# RS232toUART.net
KiCad netlist of a schematic drawn in Altium Designer
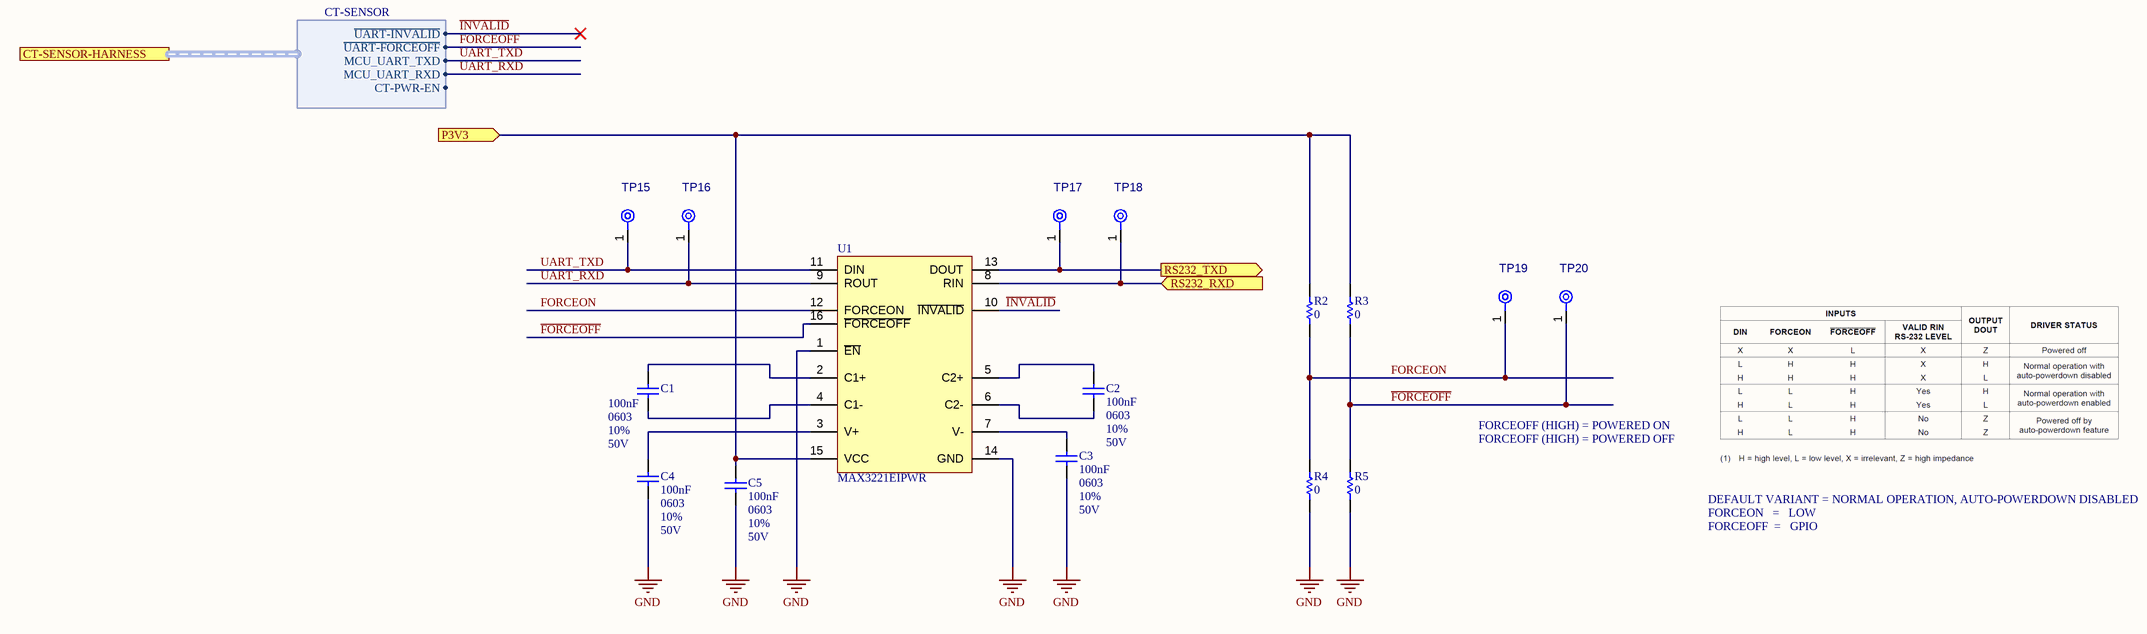
[diagram p0: RS232toUART.SchDoc]

(export (version "E")
  (design (tool "Eeschema 10.0.6"))
  (components
    (comp (ref "C1")
      (value "100nF")
      (footprint "CAPC1608X90X40ML10T20")
      (description "Chip Capacitor, 100nF, +/- 10%, 50 V, X7R 0603 (1608 Metric)")
      (fields
        (field (name "CASE/PACKAGE") "0603")
        (field (name "TOLERANCE") "10%")
        (field (name "VOLTAGE RATING") "50V")
        (field (name "Comment") "Capacitor 100nF +/- 10%, 50V, X7R, 0603")
      )
      (libsource (lib "Applied Physics Lab") (part "CAP-NP-2"))
    )
    (comp (ref "C2")
      (value "100nF")
      (footprint "CAPC1608X90X40ML10T20")
      (description "Chip Capacitor, 100nF, +/- 10%, 50 V, X7R 0603 (1608 Metric)")
      (fields
        (field (name "CASE/PACKAGE") "0603")
        (field (name "TOLERANCE") "10%")
        (field (name "VOLTAGE RATING") "50V")
        (field (name "Comment") "Capacitor 100nF +/- 10%, 50V, X7R, 0603")
      )
      (libsource (lib "Applied Physics Lab") (part "CAP-NP-2"))
    )
    (comp (ref "C3")
      (value "100nF")
      (footprint "CAPC1608X90X40ML10T20")
      (description "Chip Capacitor, 100nF, +/- 10%, 50 V, X7R 0603 (1608 Metric)")
      (fields
        (field (name "CASE/PACKAGE") "0603")
        (field (name "TOLERANCE") "10%")
        (field (name "VOLTAGE RATING") "50V")
        (field (name "Comment") "Capacitor 100nF +/- 10%, 50V, X7R, 0603")
      )
      (libsource (lib "Applied Physics Lab") (part "CAP-NP-2"))
    )
    (comp (ref "C4")
      (value "100nF")
      (footprint "CAPC1608X90X40ML10T20")
      (description "Chip Capacitor, 100nF, +/- 10%, 50 V, X7R 0603 (1608 Metric)")
      (fields
        (field (name "CASE/PACKAGE") "0603")
        (field (name "TOLERANCE") "10%")
        (field (name "VOLTAGE RATING") "50V")
        (field (name "Comment") "Capacitor 100nF +/- 10%, 50V, X7R, 0603")
      )
      (libsource (lib "Applied Physics Lab") (part "CAP-NP-2"))
    )
    (comp (ref "C5")
      (value "100nF")
      (footprint "CAPC1608X90X40ML10T20")
      (description "Chip Capacitor, 100nF, +/- 10%, 50 V, X7R 0603 (1608 Metric)")
      (fields
        (field (name "CASE/PACKAGE") "0603")
        (field (name "TOLERANCE") "10%")
        (field (name "VOLTAGE RATING") "50V")
        (field (name "Comment") "Capacitor 100nF +/- 10%, 50V, X7R, 0603")
      )
      (libsource (lib "Applied Physics Lab") (part "CAP-NP-2"))
    )
    (comp (ref "R2")
      (value "0")
      (footprint "RESC2013X50X35ML15T15")
      (description "Chip Resistor, 0 Ohm, +/- 1%, 125 mW, -55 to 155 degC, 0805 (2012 Metric)")
      (fields (field (name "TOLERANCE") "1%") (field (name "POWER") "125mW"))
      (libsource (lib "Applied Physics Lab") (part "RES-2"))
    )
    (comp (ref "R3")
      (value "0")
      (footprint "RESC2013X50X35ML15T15")
      (description "Chip Resistor, 0 Ohm, +/- 1%, 125 mW, -55 to 155 degC, 0805 (2012 Metric)")
      (fields (field (name "TOLERANCE") "1%") (field (name "POWER") "125mW"))
      (libsource (lib "Applied Physics Lab") (part "RES-2"))
    )
    (comp (ref "R4")
      (value "0")
      (footprint "RESC2013X50X35ML15T15")
      (description "Chip Resistor, 0 Ohm, +/- 1%, 125 mW, -55 to 155 degC, 0805 (2012 Metric)")
      (fields (field (name "TOLERANCE") "1%") (field (name "POWER") "125mW"))
      (libsource (lib "Applied Physics Lab") (part "RES-2"))
    )
    (comp (ref "R5")
      (value "0")
      (footprint "RESC2013X50X35ML15T15")
      (description "Chip Resistor, 0 Ohm, +/- 1%, 125 mW, -55 to 155 degC, 0805 (2012 Metric)")
      (fields (field (name "TOLERANCE") "1%") (field (name "POWER") "125mW"))
      (libsource (lib "Applied Physics Lab") (part "RES-2"))
    )
    (comp (ref "TP15")
      (value "TPAD6R-CIRCLED")
      (footprint "TP06R - Circled")
      (description "0.6mm round with a silkscreen circle.")
      (libsource (lib "Applied Physics Lab") (part "CMP-001-0001-4"))
    )
    (comp (ref "TP16")
      (value "TPAD6R-CIRCLED")
      (footprint "TP06R - Circled")
      (description "0.6mm round with a silkscreen circle.")
      (libsource (lib "Applied Physics Lab") (part "CMP-001-0001-4"))
    )
    (comp (ref "TP17")
      (value "TPAD6R-CIRCLED")
      (footprint "TP06R - Circled")
      (description "0.6mm round with a silkscreen circle.")
      (libsource (lib "Applied Physics Lab") (part "CMP-001-0001-4"))
    )
    (comp (ref "TP18")
      (value "TPAD6R-CIRCLED")
      (footprint "TP06R - Circled")
      (description "0.6mm round with a silkscreen circle.")
      (libsource (lib "Applied Physics Lab") (part "CMP-001-0001-4"))
    )
    (comp (ref "TP19")
      (value "TPAD6R-CIRCLED")
      (footprint "TP06R - Circled")
      (description "0.6mm round with a silkscreen circle.")
      (libsource (lib "Applied Physics Lab") (part "CMP-001-0001-4"))
    )
    (comp (ref "TP20")
      (value "TPAD6R-CIRCLED")
      (footprint "TP06R - Circled")
      (description "0.6mm round with a silkscreen circle.")
      (libsource (lib "Applied Physics Lab") (part "CMP-001-0001-4"))
    )
    (comp (ref "U1")
      (value "MAX3221EIPWR")
      (footprint "PW0016A_M")
      (description "IC DRVR/RCVR RS232 1CH 16-TSSOP")
      (libsource (lib "Applied Physics Lab") (part "TI-MAX3221E-TSSOP_PW-16"))
    )
  )
  (nets
    (net (code "2") (name "/FORCEON") (class "Default")
      (node (ref "R2") (pin "1") (pinfunction "1_1") (pintype "passive"))
      (node (ref "R4") (pin "2") (pinfunction "2_2") (pintype "passive"))
      (node (ref "TP19") (pin "1") (pinfunction "TP_1") (pintype "passive"))
      (node (ref "U1") (pin "12") (pinfunction "FORCEON_12") (pintype "passive"))
    )
    (net (code "3") (name "/P3V3") (class "Default")
      (node (ref "C5") (pin "2") (pinfunction "2_2") (pintype "passive"))
      (node (ref "R2") (pin "2") (pinfunction "2_2") (pintype "passive"))
      (node (ref "R3") (pin "2") (pinfunction "2_2") (pintype "passive"))
      (node (ref "U1") (pin "15") (pinfunction "VCC_15") (pintype "passive"))
    )
    (net (code "4") (name "/RS232_RXD") (class "Default")
      (node (ref "TP18") (pin "1") (pinfunction "TP_1") (pintype "passive"))
      (node (ref "U1") (pin "8") (pinfunction "RIN_8") (pintype "passive"))
    )
    (net (code "5") (name "/RS232_TXD") (class "Default")
      (node (ref "TP17") (pin "1") (pinfunction "TP_1") (pintype "passive"))
      (node (ref "U1") (pin "13") (pinfunction "DOUT_13") (pintype "passive"))
    )
    (net (code "6") (name "/UART_RXD") (class "Default")
      (node (ref "TP16") (pin "1") (pinfunction "TP_1") (pintype "passive"))
      (node (ref "U1") (pin "9") (pinfunction "ROUT_9") (pintype "passive"))
    )
    (net (code "7") (name "/UART_TXD") (class "Default")
      (node (ref "TP15") (pin "1") (pinfunction "TP_1") (pintype "passive"))
      (node (ref "U1") (pin "11") (pinfunction "DIN_11") (pintype "passive"))
    )
    (net (code "9") (name "/~{FORCEOFF}") (class "Default")
      (node (ref "R3") (pin "1") (pinfunction "1_1") (pintype "passive"))
      (node (ref "R5") (pin "2") (pinfunction "2_2") (pintype "passive"))
      (node (ref "TP20") (pin "1") (pinfunction "TP_1") (pintype "passive"))
      (node (ref "U1") (pin "16") (pinfunction "~{FORCEOFF}_16") (pintype "passive"))
    )
    (net (code "10") (name "/~{INVALID}") (class "Default")
      (node (ref "U1") (pin "10") (pinfunction "~{INVALID}_10") (pintype "passive+no_connect"))
    )
    (net (code "11") (name "GND") (class "Default")
      (node (ref "C3") (pin "1") (pinfunction "1_1") (pintype "passive"))
      (node (ref "C4") (pin "1") (pinfunction "1_1") (pintype "passive"))
      (node (ref "C5") (pin "1") (pinfunction "1_1") (pintype "passive"))
      (node (ref "R4") (pin "1") (pinfunction "1_1") (pintype "passive"))
      (node (ref "R5") (pin "1") (pinfunction "1_1") (pintype "passive"))
      (node (ref "U1") (pin "1") (pinfunction "~{EN}_1") (pintype "passive"))
      (node (ref "U1") (pin "14") (pinfunction "GND_14") (pintype "passive"))
    )
    (net (code "12") (name "Net-(U1-C1+)") (class "Default")
      (node (ref "C1") (pin "2") (pinfunction "2_2") (pintype "passive"))
      (node (ref "U1") (pin "2") (pinfunction "C1+_2") (pintype "passive"))
    )
    (net (code "13") (name "Net-(U1-C1-)") (class "Default")
      (node (ref "C1") (pin "1") (pinfunction "1_1") (pintype "passive"))
      (node (ref "U1") (pin "4") (pinfunction "C1-_4") (pintype "passive"))
    )
    (net (code "14") (name "Net-(U1-C2+)") (class "Default")
      (node (ref "C2") (pin "1") (pinfunction "1_1") (pintype "passive"))
      (node (ref "U1") (pin "5") (pinfunction "C2+_5") (pintype "passive"))
    )
    (net (code "15") (name "Net-(U1-C2-)") (class "Default")
      (node (ref "C2") (pin "2") (pinfunction "2_2") (pintype "passive"))
      (node (ref "U1") (pin "6") (pinfunction "C2-_6") (pintype "passive"))
    )
    (net (code "16") (name "Net-(U1-V+)") (class "Default")
      (node (ref "C4") (pin "2") (pinfunction "2_2") (pintype "passive"))
      (node (ref "U1") (pin "3") (pinfunction "V+_3") (pintype "passive"))
    )
    (net (code "17") (name "Net-(U1-V-)") (class "Default")
      (node (ref "C3") (pin "2") (pinfunction "2_2") (pintype "passive"))
      (node (ref "U1") (pin "7") (pinfunction "V-_7") (pintype "passive"))
    )
  )
)
